# Sheet1.net
KiCad netlist of a schematic drawn in Altium Designer
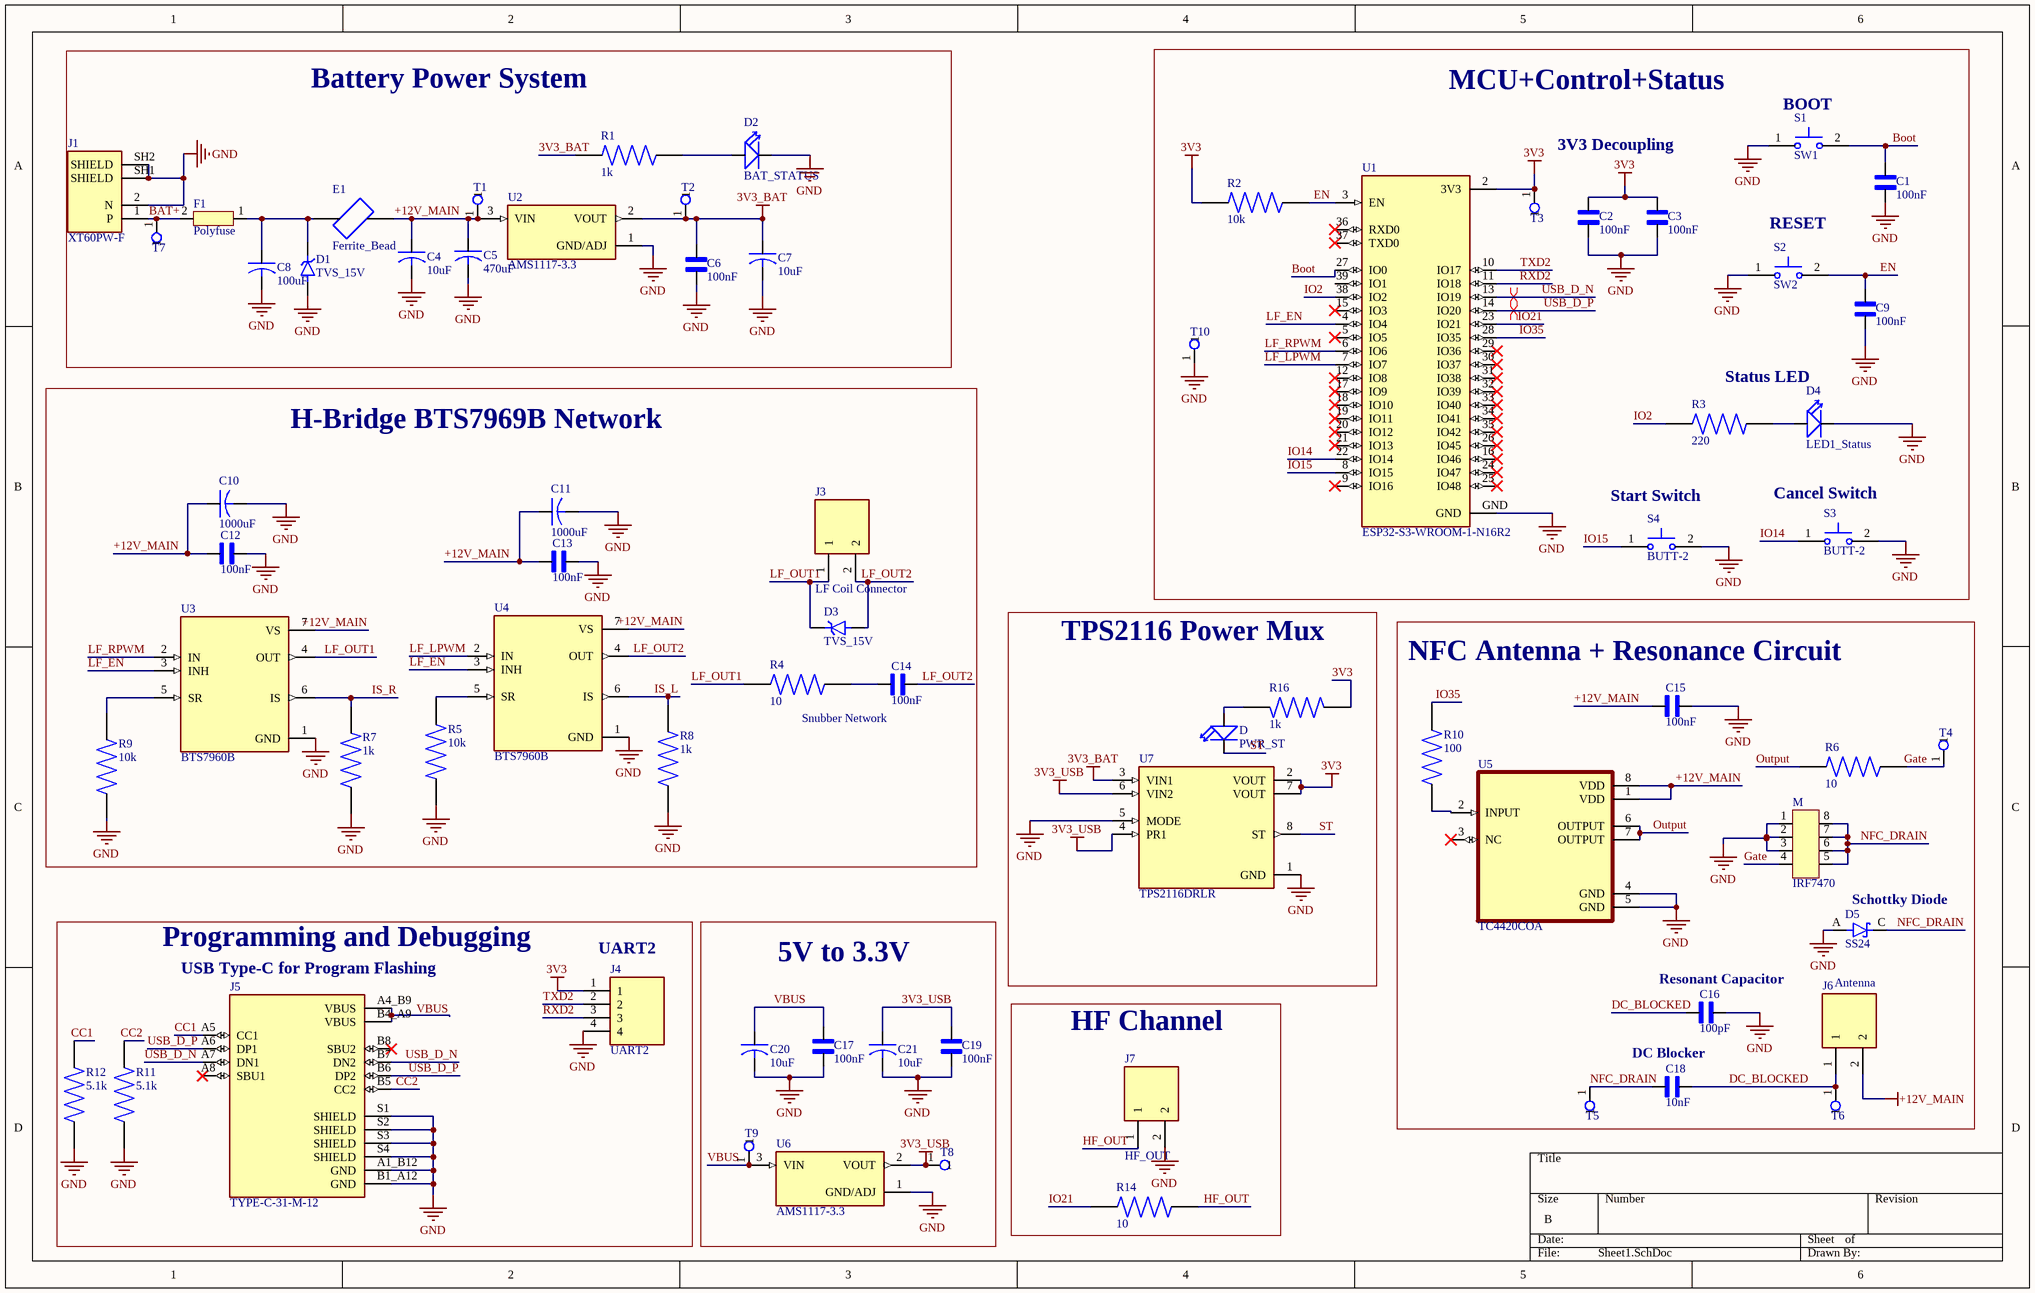
[diagram p0: Sheet1.SchDoc]

(export (version "E")
  (design (tool "Eeschema 10.0.6"))
  (components
    (comp (ref "C1")
      (value "100nF")
      (footprint "SMD_Ceramic_CAP")
      (description "10000 pF Â±5% 16V Ceramic Capacitor X7R 0805 (2012 Metric)")
      (fields (field (name "MF") "AVX") (field (name "MP") "0805YC103J4T2A"))
      (libsource (lib "Schlib1") (part "SMD_Ceramic_CAP"))
    )
    (comp (ref "C2")
      (value "100nF")
      (footprint "SMD_Ceramic_CAP")
      (description "10000 pF Â±5% 16V Ceramic Capacitor X7R 0805 (2012 Metric)")
      (fields (field (name "MF") "AVX") (field (name "MP") "0805YC103J4T2A"))
      (libsource (lib "Schlib1") (part "SMD_Ceramic_CAP"))
    )
    (comp (ref "C3")
      (value "100nF")
      (footprint "SMD_Ceramic_CAP")
      (description "10000 pF Â±5% 16V Ceramic Capacitor X7R 0805 (2012 Metric)")
      (fields (field (name "MF") "AVX") (field (name "MP") "0805YC103J4T2A"))
      (libsource (lib "Schlib1") (part "SMD_Ceramic_CAP"))
    )
    (comp (ref "C4")
      (value "10uF")
      (footprint "Capacitor_Bipolar-SMD")
      (description "<B>CAPACITOR</B>, American symbol")
      (fields (field (name "MP") "CAPACITOR"))
      (libsource (lib "Schlib1") (part "CAPACITOR"))
    )
    (comp (ref "C5")
      (value "470uF")
      (footprint "Capacitor_Bipolar-SMD")
      (description "<B>CAPACITOR</B>, American symbol")
      (fields (field (name "MP") "CAPACITOR"))
      (libsource (lib "Schlib1") (part "CAPACITOR"))
    )
    (comp (ref "C6")
      (value "100nF")
      (footprint "SMD_Ceramic_CAP")
      (description "10000 pF Â±5% 16V Ceramic Capacitor X7R 0805 (2012 Metric)")
      (fields (field (name "MF") "AVX") (field (name "MP") "0805YC103J4T2A"))
      (libsource (lib "Schlib1") (part "SMD_Ceramic_CAP"))
    )
    (comp (ref "C7")
      (value "10uF")
      (footprint "Capacitor_Bipolar-SMD")
      (description "<B>CAPACITOR</B>, American symbol")
      (fields (field (name "MP") "CAPACITOR"))
      (libsource (lib "Schlib1") (part "CAPACITOR"))
    )
    (comp (ref "C8")
      (value "100uF")
      (footprint "Capacitor_Bipolar-SMD")
      (description "<B>CAPACITOR</B>, American symbol")
      (fields (field (name "MP") "CAPACITOR"))
      (libsource (lib "Schlib1") (part "CAPACITOR"))
    )
    (comp (ref "C9")
      (value "100nF")
      (footprint "SMD_Ceramic_CAP")
      (description "10000 pF Â±5% 16V Ceramic Capacitor X7R 0805 (2012 Metric)")
      (fields (field (name "MF") "AVX") (field (name "MP") "0805YC103J4T2A"))
      (libsource (lib "Schlib1") (part "SMD_Ceramic_CAP"))
    )
    (comp (ref "C10")
      (value "1000uF")
      (footprint "Capacitor_Bipolar-SMD")
      (description "<B>CAPACITOR</B>, American symbol")
      (fields (field (name "MP") "CAPACITOR"))
      (libsource (lib "Schlib1") (part "CAPACITOR"))
    )
    (comp (ref "C11")
      (value "1000uF")
      (footprint "Capacitor_Bipolar-SMD")
      (description "<B>CAPACITOR</B>, American symbol")
      (fields (field (name "MP") "CAPACITOR"))
      (libsource (lib "Schlib1") (part "CAPACITOR"))
    )
    (comp (ref "C12")
      (value "100nF")
      (footprint "SMD_Ceramic_CAP")
      (description "10000 pF Â±5% 16V Ceramic Capacitor X7R 0805 (2012 Metric)")
      (fields (field (name "MF") "AVX") (field (name "MP") "0805YC103J4T2A"))
      (libsource (lib "") (part "SMD_Ceramic_CAP_1"))
    )
    (comp (ref "C13")
      (value "100nF")
      (footprint "SMD_Ceramic_CAP")
      (description "10000 pF Â±5% 16V Ceramic Capacitor X7R 0805 (2012 Metric)")
      (fields (field (name "MF") "AVX") (field (name "MP") "0805YC103J4T2A"))
      (libsource (lib "") (part "SMD_Ceramic_CAP_1"))
    )
    (comp (ref "C14")
      (value "100nF")
      (footprint "SMD_Ceramic_CAP")
      (description "10000 pF Â±5% 16V Ceramic Capacitor X7R 0805 (2012 Metric)")
      (fields (field (name "MF") "AVX") (field (name "MP") "0805YC103J4T2A"))
      (libsource (lib "") (part "SMD_Ceramic_CAP_1"))
    )
    (comp (ref "C15")
      (value "100nF")
      (footprint "SMD_Ceramic_CAP")
      (description "10000 pF Â±5% 16V Ceramic Capacitor X7R 0805 (2012 Metric)")
      (fields (field (name "MF") "AVX") (field (name "MP") "0805YC103J4T2A"))
      (libsource (lib "") (part "SMD_Ceramic_CAP_2"))
    )
    (comp (ref "C16")
      (value "100pF")
      (footprint "SMD_Ceramic_CAP")
      (description "10000 pF Â±5% 16V Ceramic Capacitor X7R 0805 (2012 Metric)")
      (fields (field (name "MF") "AVX") (field (name "MP") "0805YC103J4T2A"))
      (libsource (lib "") (part "SMD_Ceramic_CAP_1"))
    )
    (comp (ref "C17")
      (value "100nF")
      (footprint "SMD_Ceramic_CAP")
      (description "10000 pF Â±5% 16V Ceramic Capacitor X7R 0805 (2012 Metric)")
      (fields (field (name "MF") "AVX") (field (name "MP") "0805YC103J4T2A"))
      (libsource (lib "Schlib1") (part "SMD_Ceramic_CAP"))
    )
    (comp (ref "C18")
      (value "10nF")
      (footprint "SMD_Ceramic_CAP")
      (description "10000 pF Â±5% 16V Ceramic Capacitor X7R 0805 (2012 Metric)")
      (fields (field (name "MF") "AVX") (field (name "MP") "0805YC103J4T2A"))
      (libsource (lib "") (part "SMD_Ceramic_CAP_1"))
    )
    (comp (ref "C19")
      (value "100nF")
      (footprint "SMD_Ceramic_CAP")
      (description "10000 pF Â±5% 16V Ceramic Capacitor X7R 0805 (2012 Metric)")
      (fields (field (name "MF") "AVX") (field (name "MP") "0805YC103J4T2A"))
      (libsource (lib "Schlib1") (part "SMD_Ceramic_CAP"))
    )
    (comp (ref "C20")
      (value "10uF")
      (footprint "Capacitor_Bipolar-SMD")
      (description "<B>CAPACITOR</B>, American symbol")
      (fields (field (name "MP") "CAPACITOR"))
      (libsource (lib "Schlib1") (part "CAPACITOR"))
    )
    (comp (ref "C21")
      (value "10uF")
      (footprint "Capacitor_Bipolar-SMD")
      (description "<B>CAPACITOR</B>, American symbol")
      (fields (field (name "MP") "CAPACITOR"))
      (libsource (lib "Schlib1") (part "CAPACITOR"))
    )
    (comp (ref "D")
      (value "PWR_ST")
      (footprint "SnapEDApcb:LED-0603")
      (description "Blue LED Indication - Discrete 2.8V 0603 _1608 Metric_")
      (fields (field (name "MF") "Everlight") (field (name "MP") "19-217/BHC-ZL1M2RY/3T"))
      (libsource (lib "Schlib1") (part "SMD-LED(0603)"))
    )
    (comp (ref "D1")
      (value "TVS_15V")
      (footprint "TVS_15V")
      (description "15V Clamp 80A Ipp Tvs Diode Surface Mount SGP1610N2")
      (fields (field (name "MF") "Semtech Corporation") (field (name "MP") "UCLAMP0571P.TNT"))
      (libsource (lib "Schlib1") (part "TVS_15V"))
    )
    (comp (ref "D2")
      (value "BAT_STATUS")
      (footprint "SnapEDApcb:LED-0603")
      (description "Blue LED Indication - Discrete 2.8V 0603 _1608 Metric_")
      (fields (field (name "MF") "Everlight") (field (name "MP") "19-217/BHC-ZL1M2RY/3T"))
      (libsource (lib "Schlib1") (part "SMD-LED(0603)"))
    )
    (comp (ref "D3")
      (value "TVS_15V")
      (footprint "TVS_15V")
      (description "15V Clamp 80A Ipp Tvs Diode Surface Mount SGP1610N2")
      (fields (field (name "MF") "Semtech Corporation") (field (name "MP") "UCLAMP0571P.TNT"))
      (libsource (lib "Schlib1") (part "TVS_15V"))
    )
    (comp (ref "D4")
      (value "LED1_Status")
      (footprint "SnapEDApcb:LED-0603")
      (description "Blue LED Indication - Discrete 2.8V 0603 _1608 Metric_")
      (fields (field (name "MF") "Everlight") (field (name "MP") "19-217/BHC-ZL1M2RY/3T"))
      (libsource (lib "Schlib1") (part "SMD-LED(0603)"))
    )
    (comp (ref "D5")
      (value "SS24")
      (footprint "SS24")
      (description "Diode Schottky 40V 2A Surface Mount DO-214AA (SMB)")
      (fields (field (name "MF") "ON Semiconductor"))
      (libsource (lib "Schlib1") (part "SS24"))
    )
    (comp (ref "E1")
      (value "Ferrite_Bead")
      (footprint "Ferrite_bead")
      (description "120 Ohms @ 100 MHz 1 Power, Signal Line Ferrite Bead 0603 (1608 Metric) 700mA 200mOhm")
      (fields (field (name "MF") "Laird") (field (name "MP") "LI0603G121R-10"))
      (libsource (lib "Schlib1") (part "Ferrite_Bead"))
    )
    (comp (ref "F1") (value "Polyfuse") (footprint "Polyfuse") (libsource (lib "Schlib1") (part "Polyfuse")))
    (comp (ref "J1")
      (value "XT60PW-F")
      (footprint "XT60PW-F")
      (description "Connector: DC supply; socket; female; XT60; 30A; 500V; PIN: 2; THT")
      (fields (field (name "MF") "AMASS"))
      (libsource (lib "Schlib1") (part "XT60PW-F"))
    )
    (comp (ref "J3")
      (value "LF Coil Connector")
      (footprint "2_Pin_Terminal_Block")
      (description "2 Pin Terminal Block 5mm Pitch")
      (fields (field (name "MF") "Handson Technology") (field (name "MP") "KF301-2P"))
      (libsource (lib "Schlib1") (part "2_Pin_Terminal_Block"))
    )
    (comp (ref "J4")
      (value "UART2")
      (footprint "JST_XH_Balance")
      (description "MTA-100 HEADER - TIN, 04P MTA100 HDR ASSY SQ R/A POL ¦ TE Connectivity 640455-4")
      (fields (field (name "MF") "TE Connectivity") (field (name "MP") "640455-4"))
      (libsource (lib "Schlib1") (part "4_pin_header"))
    )
    (comp (ref "J5")
      (value "TYPE-C-31-M-12")
      (footprint "HRO_TYPE-C-31-M-12")
      (description "USB Connectors 24 Receptacle 1 8.94*7.3mm RoHS")
      (fields (field (name "MF") "HRO Electronics Co., Ltd."))
      (libsource (lib "Schlib1") (part "TYPE-C-31-M-12"))
    )
    (comp (ref "J6")
      (value "Antenna")
      (footprint "2_Pin_Terminal_Block")
      (description "2 Pin Terminal Block 5mm Pitch")
      (fields (field (name "MF") "Handson Technology") (field (name "MP") "KF301-2P"))
      (libsource (lib "Schlib1") (part "2_Pin_Terminal_Block"))
    )
    (comp (ref "J7")
      (value "HF_OUT")
      (footprint "2_Pin_Terminal_Block")
      (description "2 Pin Terminal Block 5mm Pitch")
      (fields (field (name "MF") "Handson Technology") (field (name "MP") "KF301-2P"))
      (libsource (lib "Schlib1") (part "2_Pin_Terminal_Block"))
    )
    (comp (ref "M") (value "IRF7470") (footprint "IRF7470") (libsource (lib "Schlib1") (part "IRF7470")))
    (comp (ref "R1")
      (value "1k")
      (footprint "Resistor_SMD")
      (description "1 kOhms Â±0.5% 0.063W, 1/16W Chip Resistor 0603 (1608 Metric) - Thin Film")
      (fields (field (name "MF") "Susumu") (field (name "MP") "RR0816P-102-D"))
      (libsource (lib "Schlib1") (part "Resisto_SMD"))
    )
    (comp (ref "R2")
      (value "10k")
      (footprint "Resistor_SMD")
      (description "1 kOhms Â±0.5% 0.063W, 1/16W Chip Resistor 0603 (1608 Metric) - Thin Film")
      (fields (field (name "MF") "Susumu") (field (name "MP") "RR0816P-102-D"))
      (libsource (lib "Schlib1") (part "Resistor_SMD"))
    )
    (comp (ref "R3")
      (value "220")
      (footprint "Resistor_SMD")
      (description "1 kOhms Â±0.5% 0.063W, 1/16W Chip Resistor 0603 (1608 Metric) - Thin Film")
      (fields (field (name "MF") "Susumu") (field (name "MP") "RR0816P-102-D"))
      (libsource (lib "Schlib1") (part "Resistor_SMD"))
    )
    (comp (ref "R4")
      (value "10")
      (footprint "Resistor_SMD")
      (description "1 kOhms Â±0.5% 0.063W, 1/16W Chip Resistor 0603 (1608 Metric) - Thin Film")
      (fields (field (name "MF") "Susumu") (field (name "MP") "RR0816P-102-D"))
      (libsource (lib "Schlib1") (part "Resistor_SMD"))
    )
    (comp (ref "R5")
      (value "10k")
      (footprint "Resistor_SMD")
      (description "1 kOhms Â±0.5% 0.063W, 1/16W Chip Resistor 0603 (1608 Metric) - Thin Film")
      (fields (field (name "MF") "Susumu") (field (name "MP") "RR0816P-102-D"))
      (libsource (lib "Schlib1") (part "Resistor_SMD"))
    )
    (comp (ref "R6")
      (value "10")
      (footprint "Resistor_SMD")
      (description "1 kOhms Â±0.5% 0.063W, 1/16W Chip Resistor 0603 (1608 Metric) - Thin Film")
      (fields (field (name "MF") "Susumu") (field (name "MP") "RR0816P-102-D"))
      (libsource (lib "Schlib1") (part "Resistor_SMD"))
    )
    (comp (ref "R7")
      (value "1k")
      (footprint "Resistor_SMD")
      (description "1 kOhms Â±0.5% 0.063W, 1/16W Chip Resistor 0603 (1608 Metric) - Thin Film")
      (fields (field (name "MF") "Susumu") (field (name "MP") "RR0816P-102-D"))
      (libsource (lib "Schlib1") (part "Resistor_SMD"))
    )
    (comp (ref "R8")
      (value "1k")
      (footprint "Resistor_SMD")
      (description "1 kOhms Â±0.5% 0.063W, 1/16W Chip Resistor 0603 (1608 Metric) - Thin Film")
      (fields (field (name "MF") "Susumu") (field (name "MP") "RR0816P-102-D"))
      (libsource (lib "Schlib1") (part "Resistor_SMD"))
    )
    (comp (ref "R9")
      (value "10k")
      (footprint "Resistor_SMD")
      (description "1 kOhms Â±0.5% 0.063W, 1/16W Chip Resistor 0603 (1608 Metric) - Thin Film")
      (fields (field (name "MF") "Susumu") (field (name "MP") "RR0816P-102-D"))
      (libsource (lib "Schlib1") (part "Resistor_SMD"))
    )
    (comp (ref "R10")
      (value "100")
      (footprint "Resistor_SMD")
      (description "1 kOhms Â±0.5% 0.063W, 1/16W Chip Resistor 0603 (1608 Metric) - Thin Film")
      (fields (field (name "MF") "Susumu") (field (name "MP") "RR0816P-102-D"))
      (libsource (lib "Schlib1") (part "Resistor_SMD"))
    )
    (comp (ref "R11")
      (value "5.1k")
      (footprint "Resistor_SMD")
      (description "1 kOhms Â±0.5% 0.063W, 1/16W Chip Resistor 0603 (1608 Metric) - Thin Film")
      (fields (field (name "MF") "Susumu") (field (name "MP") "RR0816P-102-D"))
      (libsource (lib "Schlib1") (part "Resistor_SMD"))
    )
    (comp (ref "R12")
      (value "5.1k")
      (footprint "Resistor_SMD")
      (description "1 kOhms Â±0.5% 0.063W, 1/16W Chip Resistor 0603 (1608 Metric) - Thin Film")
      (fields (field (name "MF") "Susumu") (field (name "MP") "RR0816P-102-D"))
      (libsource (lib "Schlib1") (part "Resistor_SMD"))
    )
    (comp (ref "R14")
      (value "10")
      (footprint "Resistor_SMD")
      (description "1 kOhms Â±0.5% 0.063W, 1/16W Chip Resistor 0603 (1608 Metric) - Thin Film")
      (fields (field (name "MF") "Susumu") (field (name "MP") "RR0816P-102-D"))
      (libsource (lib "Schlib1") (part "Resistor_SMD"))
    )
    (comp (ref "R16")
      (value "1k")
      (footprint "Resistor_SMD")
      (description "1 kOhms Â±0.5% 0.063W, 1/16W Chip Resistor 0603 (1608 Metric) - Thin Film")
      (fields (field (name "MF") "Susumu") (field (name "MP") "RR0816P-102-D"))
      (libsource (lib "Schlib1") (part "Resistor_SMD"))
    )
    (comp (ref "S1")
      (value "SW1")
      (footprint "SW_BUTT-2")
      (description "Tactile Switches MINI PUSH BUTTON SWITCH 2-PIN QTY. 4")
      (fields (field (name "MF") "Gravitech") (field (name "MP") "BUTT-2"))
      (libsource (lib "Schlib1") (part "BUTT-2"))
    )
    (comp (ref "S2")
      (value "SW2")
      (footprint "SW_BUTT-2")
      (description "Tactile Switches MINI PUSH BUTTON SWITCH 2-PIN QTY. 4")
      (fields (field (name "MF") "Gravitech") (field (name "MP") "BUTT-2"))
      (libsource (lib "Schlib1") (part "BUTT-2"))
    )
    (comp (ref "S3")
      (value "BUTT-2")
      (footprint "SW_BUTT-2")
      (description "Tactile Switches MINI PUSH BUTTON SWITCH 2-PIN QTY. 4")
      (fields (field (name "MF") "Gravitech"))
      (libsource (lib "Schlib1") (part "BUTT-2"))
    )
    (comp (ref "S4")
      (value "BUTT-2")
      (footprint "SW_BUTT-2")
      (description "Tactile Switches MINI PUSH BUTTON SWITCH 2-PIN QTY. 4")
      (fields (field (name "MF") "Gravitech"))
      (libsource (lib "Schlib1") (part "BUTT-2"))
    )
    (comp (ref "T1")
      (value "Test_Point")
      (footprint "Test_Point")
      (libsource (lib "Schlib1") (part "Test_Point"))
    )
    (comp (ref "T2")
      (value "Test_Point")
      (footprint "Test_Point")
      (libsource (lib "Schlib1") (part "Test_Point"))
    )
    (comp (ref "T3")
      (value "Test_Point")
      (footprint "Test_Point")
      (libsource (lib "Schlib1") (part "Test_Point"))
    )
    (comp (ref "T4")
      (value "Test_Point")
      (footprint "Test_Point")
      (libsource (lib "Schlib1") (part "Test_Point"))
    )
    (comp (ref "T5")
      (value "Test_Point")
      (footprint "Test_Point")
      (libsource (lib "Schlib1") (part "Test_Point"))
    )
    (comp (ref "T6")
      (value "Test_Point")
      (footprint "Test_Point")
      (libsource (lib "Schlib1") (part "Test_Point"))
    )
    (comp (ref "T7")
      (value "Test_Point")
      (footprint "Test_Point")
      (libsource (lib "Schlib1") (part "Test_Point"))
    )
    (comp (ref "T8")
      (value "Test_Point")
      (footprint "Test_Point")
      (libsource (lib "Schlib1") (part "Test_Point"))
    )
    (comp (ref "T9")
      (value "Test_Point")
      (footprint "Test_Point")
      (libsource (lib "Schlib1") (part "Test_Point"))
    )
    (comp (ref "T10")
      (value "Test_Point")
      (footprint "Test_Point")
      (libsource (lib "Schlib1") (part "Test_Point"))
    )
    (comp (ref "U1")
      (value "ESP32-S3-WROOM-1-N16R2")
      (footprint "ESP32-S3-WROOM-1-N16R2")
      (description "Bluetooth, WiFi 802.11b/g/n, Bluetooth v5.0 Transceiver Module 2.4GHz PCB Trace Surface Mount")
      (fields (field (name "MF") "Espressif Systems") (field (name "MP") "ESP32S3WROOM1N16R2"))
      (libsource (lib "Schlib1") (part "ESP32-S3-WROOM-1-N16R2"))
    )
    (comp (ref "U2")
      (value "AMS1117-3.3")
      (footprint "AMS1117-5.0")
      (description "1A LOW DROPOUT VOLTAGE REGULATOR")
      (fields (field (name "MP") "AMS1117-5.0") (field (name "MF") "ams"))
      (libsource (lib "Schlib1") (part "AMS1117-5.0"))
    )
    (comp (ref "U3")
      (value "BTS7960B")
      (footprint "BTS7960B")
      (description "Half Bridge Driver DC Motors, General Purpose DMOS PG-TO263-7-1")
      (fields (field (name "MF") "Infineon"))
      (libsource (lib "Schlib1") (part "BTS7960B"))
    )
    (comp (ref "U4")
      (value "BTS7960B")
      (footprint "BTS7960B")
      (description "Half Bridge Driver DC Motors, General Purpose DMOS PG-TO263-7-1")
      (fields (field (name "MF") "Infineon"))
      (libsource (lib "Schlib1") (part "BTS7960B"))
    )
    (comp (ref "U5")
      (value "TC4420COA")
      (footprint "TC4420COA")
      (fields (field (name "MF") "Microchip Technology"))
      (libsource (lib "Schlib1") (part "TC4420COA"))
    )
    (comp (ref "U6")
      (value "AMS1117-3.3")
      (footprint "AMS1117-5.0")
      (description "1A LOW DROPOUT VOLTAGE REGULATOR")
      (fields (field (name "MP") "AMS1117-5.0") (field (name "MF") "ams"))
      (libsource (lib "Schlib1") (part "AMS1117-5.0"))
    )
    (comp (ref "U7")
      (value "TPS2116DRLR")
      (footprint "TPS2116")
      (description "1.6-V to 5.5-V, 40-mâ„¦, 2.5-A, low-IQ, priority power multiplexer")
      (fields (field (name "MF") "Texas Instruments"))
      (libsource (lib "Schlib1") (part "TPS2116DRLR"))
    )
  )
  (nets
    (net (code "1") (name "+12V_MAIN") (class "Default")
      (node (ref "C10") (pin "1") (pinfunction "1_1") (pintype "passive"))
      (node (ref "C11") (pin "1") (pinfunction "1_1") (pintype "passive"))
      (node (ref "C12") (pin "1") (pinfunction "1_1") (pintype "passive"))
      (node (ref "C13") (pin "1") (pinfunction "1_1") (pintype "passive"))
      (node (ref "C15") (pin "2") (pinfunction "2_2") (pintype "passive"))
      (node (ref "C4") (pin "1") (pinfunction "1_1") (pintype "passive"))
      (node (ref "C5") (pin "1") (pinfunction "1_1") (pintype "passive"))
      (node (ref "E1") (pin "2") (pinfunction "2_2") (pintype "passive"))
      (node (ref "J6") (pin "2") (pinfunction "2_2") (pintype "passive"))
      (node (ref "T1") (pin "1") (pinfunction "1_1") (pintype "passive"))
      (node (ref "U2") (pin "3") (pinfunction "VIN_3") (pintype "input"))
      (node (ref "U3") (pin "7") (pinfunction "VS_7") (pintype "power_in"))
      (node (ref "U4") (pin "7") (pinfunction "VS_7") (pintype "power_in"))
      (node (ref "U5") (pin "1") (pinfunction "VDD_1") (pintype "power_in"))
      (node (ref "U5") (pin "8") (pinfunction "VDD_8") (pintype "power_in"))
    )
    (net (code "3") (name "/BAT+") (class "Default")
      (node (ref "F1") (pin "2") (pinfunction "2_2") (pintype "passive"))
      (node (ref "J1") (pin "1") (pinfunction "P_1") (pintype "passive"))
      (node (ref "T7") (pin "1") (pinfunction "1_1") (pintype "passive"))
    )
    (net (code "4") (name "/Boot") (class "Default")
      (node (ref "C1") (pin "2") (pinfunction "2_2") (pintype "passive"))
      (node (ref "S1") (pin "2") (pinfunction "2_2") (pintype "passive"))
      (node (ref "U1") (pin "27") (pinfunction "IO0_27") (pintype "bidirectional"))
    )
    (net (code "5") (name "/CC1") (class "Default")
      (node (ref "J5") (pin "A5") (pinfunction "CC1_A5") (pintype "bidirectional"))
      (node (ref "R12") (pin "2") (pinfunction "2_2") (pintype "passive"))
    )
    (net (code "6") (name "/CC2") (class "Default")
      (node (ref "J5") (pin "B5") (pinfunction "CC2_B5") (pintype "bidirectional"))
      (node (ref "R11") (pin "2") (pinfunction "2_2") (pintype "passive"))
    )
    (net (code "7") (name "/DC_BLOCKED") (class "Default")
      (node (ref "C16") (pin "1") (pinfunction "1_1") (pintype "passive"))
      (node (ref "C18") (pin "2") (pinfunction "2_2") (pintype "passive"))
      (node (ref "J6") (pin "1") (pinfunction "1_1") (pintype "passive"))
      (node (ref "T6") (pin "1") (pinfunction "1_1") (pintype "passive"))
    )
    (net (code "8") (name "/EN") (class "Default")
      (node (ref "C9") (pin "2") (pinfunction "2_2") (pintype "passive"))
      (node (ref "R2") (pin "2") (pinfunction "2_2") (pintype "passive"))
      (node (ref "S2") (pin "2") (pinfunction "2_2") (pintype "passive"))
      (node (ref "U1") (pin "3") (pinfunction "EN_3") (pintype "input"))
    )
    (net (code "9") (name "/Gate") (class "Default")
      (node (ref "M") (pin "4") (pintype "power_in"))
      (node (ref "R6") (pin "2") (pinfunction "2_2") (pintype "passive"))
      (node (ref "T4") (pin "1") (pinfunction "1_1") (pintype "passive"))
    )
    (net (code "10") (name "/HF_OUT") (class "Default")
      (node (ref "J7") (pin "1") (pinfunction "1_1") (pintype "passive"))
      (node (ref "R14") (pin "2") (pinfunction "2_2") (pintype "passive"))
    )
    (net (code "11") (name "/IO2") (class "Default")
      (node (ref "R3") (pin "1") (pinfunction "1_1") (pintype "passive"))
      (node (ref "U1") (pin "38") (pinfunction "IO2_38") (pintype "bidirectional"))
    )
    (net (code "12") (name "/IO14") (class "Default")
      (node (ref "S3") (pin "1") (pinfunction "1_1") (pintype "passive"))
      (node (ref "U1") (pin "22") (pinfunction "IO14_22") (pintype "bidirectional"))
    )
    (net (code "13") (name "/IO15") (class "Default")
      (node (ref "S4") (pin "1") (pinfunction "1_1") (pintype "passive"))
      (node (ref "U1") (pin "8") (pinfunction "IO15_8") (pintype "bidirectional"))
    )
    (net (code "14") (name "/IO21") (class "Default")
      (node (ref "R14") (pin "1") (pinfunction "1_1") (pintype "passive"))
      (node (ref "U1") (pin "23") (pinfunction "IO21_23") (pintype "bidirectional"))
    )
    (net (code "15") (name "/IO35") (class "Default")
      (node (ref "R10") (pin "1") (pinfunction "1_1") (pintype "passive"))
      (node (ref "U1") (pin "28") (pinfunction "IO35_28") (pintype "bidirectional"))
    )
    (net (code "16") (name "/IS_L") (class "Default")
      (node (ref "R8") (pin "2") (pinfunction "2_2") (pintype "passive"))
      (node (ref "U4") (pin "6") (pinfunction "IS_6") (pintype "output"))
    )
    (net (code "17") (name "/IS_R") (class "Default")
      (node (ref "R7") (pin "2") (pinfunction "2_2") (pintype "passive"))
      (node (ref "U3") (pin "6") (pinfunction "IS_6") (pintype "output"))
    )
    (net (code "18") (name "/LF_EN") (class "Default")
      (node (ref "U1") (pin "4") (pinfunction "IO4_4") (pintype "bidirectional"))
      (node (ref "U3") (pin "3") (pinfunction "INH_3") (pintype "input"))
      (node (ref "U4") (pin "3") (pinfunction "INH_3") (pintype "input"))
    )
    (net (code "19") (name "/LF_LPWM") (class "Default")
      (node (ref "U1") (pin "7") (pinfunction "IO7_7") (pintype "bidirectional"))
      (node (ref "U4") (pin "2") (pinfunction "IN_2") (pintype "input"))
    )
    (net (code "20") (name "/LF_OUT1") (class "Default")
      (node (ref "D3") (pin "K") (pinfunction "K_K") (pintype "passive"))
      (node (ref "J3") (pin "1") (pinfunction "1_1") (pintype "passive"))
      (node (ref "R4") (pin "1") (pinfunction "1_1") (pintype "passive"))
      (node (ref "U3") (pin "4") (pinfunction "OUT_4") (pintype "output"))
    )
    (net (code "21") (name "/LF_OUT2") (class "Default")
      (node (ref "C14") (pin "2") (pinfunction "2_2") (pintype "passive"))
      (node (ref "D3") (pin "A") (pinfunction "A_A") (pintype "passive"))
      (node (ref "J3") (pin "2") (pinfunction "2_2") (pintype "passive"))
      (node (ref "U4") (pin "4") (pinfunction "OUT_4") (pintype "output"))
    )
    (net (code "22") (name "/LF_RPWM") (class "Default")
      (node (ref "U1") (pin "6") (pinfunction "IO6_6") (pintype "bidirectional"))
      (node (ref "U3") (pin "2") (pinfunction "IN_2") (pintype "input"))
    )
    (net (code "23") (name "/NFC_DRAIN") (class "Default")
      (node (ref "C18") (pin "1") (pinfunction "1_1") (pintype "passive"))
      (node (ref "D5") (pin "C") (pinfunction "K_C") (pintype "passive"))
      (node (ref "M") (pin "5") (pintype "power_in"))
      (node (ref "M") (pin "6") (pintype "power_in"))
      (node (ref "M") (pin "7") (pintype "power_in"))
      (node (ref "M") (pin "8") (pintype "power_in"))
      (node (ref "T5") (pin "1") (pinfunction "1_1") (pintype "passive"))
    )
    (net (code "24") (name "/Output") (class "Default")
      (node (ref "R6") (pin "1") (pinfunction "1_1") (pintype "passive"))
      (node (ref "U5") (pin "6") (pinfunction "OUTPUT_6") (pintype "power_in"))
      (node (ref "U5") (pin "7") (pinfunction "OUTPUT_7") (pintype "power_in"))
    )
    (net (code "25") (name "/RXD2") (class "Default")
      (node (ref "J4") (pin "3") (pinfunction "3_3") (pintype "passive"))
      (node (ref "U1") (pin "11") (pinfunction "IO18_11") (pintype "bidirectional"))
    )
    (net (code "26") (name "/ST") (class "Default")
      (node (ref "D") (pin "NEG") (pinfunction "NEG_NEG") (pintype "passive"))
      (node (ref "U7") (pin "8") (pinfunction "ST_8") (pintype "output"))
    )
    (net (code "27") (name "/TXD2") (class "Default")
      (node (ref "J4") (pin "2") (pinfunction "2_2") (pintype "passive"))
      (node (ref "U1") (pin "10") (pinfunction "IO17_10") (pintype "bidirectional"))
    )
    (net (code "28") (name "/USB_D_N") (class "Default")
      (node (ref "J5") (pin "A7") (pinfunction "DN1_A7") (pintype "bidirectional"))
      (node (ref "J5") (pin "B7") (pinfunction "DN2_B7") (pintype "bidirectional"))
      (node (ref "U1") (pin "13") (pinfunction "IO19_13") (pintype "bidirectional"))
    )
    (net (code "29") (name "/USB_D_P") (class "Default")
      (node (ref "J5") (pin "A6") (pinfunction "DP1_A6") (pintype "bidirectional"))
      (node (ref "J5") (pin "B6") (pinfunction "DP2_B6") (pintype "bidirectional"))
      (node (ref "U1") (pin "14") (pinfunction "IO20_14") (pintype "bidirectional"))
    )
    (net (code "30") (name "/VBUS") (class "Default")
      (node (ref "C17") (pin "2") (pinfunction "2_2") (pintype "passive"))
      (node (ref "C20") (pin "1") (pinfunction "1_1") (pintype "passive"))
      (node (ref "J5") (pin "A4_B9") (pinfunction "VBUS_A4_B9") (pintype "power_in"))
      (node (ref "J5") (pin "B4_A9") (pinfunction "VBUS_B4_A9") (pintype "power_in"))
      (node (ref "T9") (pin "1") (pinfunction "1_1") (pintype "passive"))
      (node (ref "U6") (pin "3") (pinfunction "VIN_3") (pintype "input"))
    )
    (net (code "31") (name "3V3") (class "Default")
      (node (ref "C2") (pin "2") (pinfunction "2_2") (pintype "passive"))
      (node (ref "C3") (pin "2") (pinfunction "2_2") (pintype "passive"))
      (node (ref "J4") (pin "1") (pinfunction "1_1") (pintype "passive"))
      (node (ref "R16") (pin "1") (pinfunction "1_1") (pintype "passive"))
      (node (ref "R2") (pin "1") (pinfunction "1_1") (pintype "passive"))
      (node (ref "T3") (pin "1") (pinfunction "1_1") (pintype "passive"))
      (node (ref "U1") (pin "2") (pinfunction "3V3_2") (pintype "power_in"))
      (node (ref "U7") (pin "2") (pinfunction "VOUT_2") (pintype "power_in"))
      (node (ref "U7") (pin "7") (pinfunction "VOUT_7") (pintype "power_in"))
    )
    (net (code "32") (name "3V3_BAT") (class "Default")
      (node (ref "C6") (pin "2") (pinfunction "2_2") (pintype "passive"))
      (node (ref "C7") (pin "1") (pinfunction "1_1") (pintype "passive"))
      (node (ref "R1") (pin "1") (pinfunction "1_1") (pintype "passive"))
      (node (ref "T2") (pin "1") (pinfunction "1_1") (pintype "passive"))
      (node (ref "U2") (pin "2") (pinfunction "VOUT_2") (pintype "output"))
      (node (ref "U7") (pin "3") (pinfunction "VIN1_3") (pintype "input"))
    )
    (net (code "33") (name "3V3_USB") (class "Default")
      (node (ref "C19") (pin "2") (pinfunction "2_2") (pintype "passive"))
      (node (ref "C21") (pin "1") (pinfunction "1_1") (pintype "passive"))
      (node (ref "T8") (pin "1") (pinfunction "1_1") (pintype "passive"))
      (node (ref "U6") (pin "2") (pinfunction "VOUT_2") (pintype "output"))
      (node (ref "U7") (pin "4") (pinfunction "PR1_4") (pintype "input"))
      (node (ref "U7") (pin "6") (pinfunction "VIN2_6") (pintype "input"))
    )
    (net (code "34") (name "GND") (class "Default")
      (node (ref "C1") (pin "1") (pinfunction "1_1") (pintype "passive"))
      (node (ref "C10") (pin "2") (pinfunction "2_2") (pintype "passive"))
      (node (ref "C11") (pin "2") (pinfunction "2_2") (pintype "passive"))
      (node (ref "C12") (pin "2") (pinfunction "2_2") (pintype "passive"))
      (node (ref "C13") (pin "2") (pinfunction "2_2") (pintype "passive"))
      (node (ref "C15") (pin "1") (pinfunction "1_1") (pintype "passive"))
      (node (ref "C16") (pin "2") (pinfunction "2_2") (pintype "passive"))
      (node (ref "C17") (pin "1") (pinfunction "1_1") (pintype "passive"))
      (node (ref "C19") (pin "1") (pinfunction "1_1") (pintype "passive"))
      (node (ref "C2") (pin "1") (pinfunction "1_1") (pintype "passive"))
      (node (ref "C20") (pin "2") (pinfunction "2_2") (pintype "passive"))
      (node (ref "C21") (pin "2") (pinfunction "2_2") (pintype "passive"))
      (node (ref "C3") (pin "1") (pinfunction "1_1") (pintype "passive"))
      (node (ref "C4") (pin "2") (pinfunction "2_2") (pintype "passive"))
      (node (ref "C5") (pin "2") (pinfunction "2_2") (pintype "passive"))
      (node (ref "C6") (pin "1") (pinfunction "1_1") (pintype "passive"))
      (node (ref "C7") (pin "2") (pinfunction "2_2") (pintype "passive"))
      (node (ref "C8") (pin "2") (pinfunction "2_2") (pintype "passive"))
      (node (ref "C9") (pin "1") (pinfunction "1_1") (pintype "passive"))
      (node (ref "D1") (pin "A") (pinfunction "A_A") (pintype "passive"))
      (node (ref "D2") (pin "NEG") (pinfunction "NEG_NEG") (pintype "passive"))
      (node (ref "D4") (pin "NEG") (pinfunction "NEG_NEG") (pintype "passive"))
      (node (ref "D5") (pin "A") (pinfunction "A_A") (pintype "passive"))
      (node (ref "J1") (pin "2") (pinfunction "N_2") (pintype "passive"))
      (node (ref "J1") (pin "SH1") (pinfunction "SHIELD_SH1") (pintype "passive"))
      (node (ref "J1") (pin "SH2") (pinfunction "SHIELD_SH2") (pintype "passive"))
      (node (ref "J4") (pin "4") (pinfunction "4_4") (pintype "passive"))
      (node (ref "J5") (pin "A1_B12") (pinfunction "GND_A1_B12") (pintype "power_in"))
      (node (ref "J5") (pin "B1_A12") (pinfunction "GND_B1_A12") (pintype "power_in"))
      (node (ref "J5") (pin "S1") (pinfunction "SHIELD_S1") (pintype "passive"))
      (node (ref "J5") (pin "S2") (pinfunction "SHIELD_S2") (pintype "passive"))
      (node (ref "J5") (pin "S3") (pinfunction "SHIELD_S3") (pintype "passive"))
      (node (ref "J5") (pin "S4") (pinfunction "SHIELD_S4") (pintype "passive"))
      (node (ref "J7") (pin "2") (pinfunction "2_2") (pintype "passive"))
      (node (ref "M") (pin "1") (pintype "power_in"))
      (node (ref "M") (pin "2") (pintype "power_in"))
      (node (ref "M") (pin "3") (pintype "power_in"))
      (node (ref "R11") (pin "1") (pinfunction "1_1") (pintype "passive"))
      (node (ref "R12") (pin "1") (pinfunction "1_1") (pintype "passive"))
      (node (ref "R5") (pin "1") (pinfunction "1_1") (pintype "passive"))
      (node (ref "R7") (pin "1") (pinfunction "1_1") (pintype "passive"))
      (node (ref "R8") (pin "1") (pinfunction "1_1") (pintype "passive"))
      (node (ref "R9") (pin "1") (pinfunction "1_1") (pintype "passive"))
      (node (ref "S1") (pin "1") (pinfunction "1_1") (pintype "passive"))
      (node (ref "S2") (pin "1") (pinfunction "1_1") (pintype "passive"))
      (node (ref "S3") (pin "2") (pinfunction "2_2") (pintype "passive"))
      (node (ref "S4") (pin "2") (pinfunction "2_2") (pintype "passive"))
      (node (ref "T10") (pin "1") (pinfunction "1_1") (pintype "passive"))
      (node (ref "U1") (pin "GND") (pinfunction "GND_GND") (pintype "power_in"))
      (node (ref "U2") (pin "1") (pinfunction "GND/ADJ_1") (pintype "power_in"))
      (node (ref "U3") (pin "1") (pinfunction "GND_1") (pintype "power_in"))
      (node (ref "U4") (pin "1") (pinfunction "GND_1") (pintype "power_in"))
      (node (ref "U5") (pin "4") (pinfunction "GND_4") (pintype "power_in"))
      (node (ref "U5") (pin "5") (pinfunction "GND_5") (pintype "power_in"))
      (node (ref "U6") (pin "1") (pinfunction "GND/ADJ_1") (pintype "power_in"))
      (node (ref "U7") (pin "1") (pinfunction "GND_1") (pintype "power_in"))
      (node (ref "U7") (pin "5") (pinfunction "MODE_5") (pintype "input"))
    )
    (net (code "35") (name "Net-(C8-Pad1)") (class "Default")
      (node (ref "C8") (pin "1") (pinfunction "1_1") (pintype "passive"))
      (node (ref "D1") (pin "K") (pinfunction "K_K") (pintype "passive"))
      (node (ref "E1") (pin "1") (pinfunction "1_1") (pintype "passive"))
      (node (ref "F1") (pin "1") (pinfunction "1_1") (pintype "passive"))
    )
    (net (code "36") (name "Net-(C14-Pad1)") (class "Default")
      (node (ref "C14") (pin "1") (pinfunction "1_1") (pintype "passive"))
      (node (ref "R4") (pin "2") (pinfunction "2_2") (pintype "passive"))
    )
    (net (code "37") (name "Net-(D-PadPOS)") (class "Default")
      (node (ref "D") (pin "POS") (pinfunction "POS_POS") (pintype "passive"))
      (node (ref "R16") (pin "2") (pinfunction "2_2") (pintype "passive"))
    )
    (net (code "38") (name "Net-(D2-PadPOS)") (class "Default")
      (node (ref "D2") (pin "POS") (pinfunction "POS_POS") (pintype "passive"))
      (node (ref "R1") (pin "2") (pinfunction "2_2") (pintype "passive"))
    )
    (net (code "39") (name "Net-(D4-PadPOS)") (class "Default")
      (node (ref "D4") (pin "POS") (pinfunction "POS_POS") (pintype "passive"))
      (node (ref "R3") (pin "2") (pinfunction "2_2") (pintype "passive"))
    )
    (net (code "40") (name "Net-(U3-SR)") (class "Default")
      (node (ref "R9") (pin "2") (pinfunction "2_2") (pintype "passive"))
      (node (ref "U3") (pin "5") (pinfunction "SR_5") (pintype "input"))
    )
    (net (code "41") (name "Net-(U4-SR)") (class "Default")
      (node (ref "R5") (pin "2") (pinfunction "2_2") (pintype "passive"))
      (node (ref "U4") (pin "5") (pinfunction "SR_5") (pintype "input"))
    )
    (net (code "42") (name "Net-(U5-INPUT)") (class "Default")
      (node (ref "R10") (pin "2") (pinfunction "2_2") (pintype "passive"))
      (node (ref "U5") (pin "2") (pinfunction "INPUT_2") (pintype "input"))
    )
    (net (code "43") (name "unconnected-(J5-SBU1-PadA8)") (class "Default")
      (node (ref "J5") (pin "A8") (pinfunction "SBU1_A8") (pintype "bidirectional+no_connect"))
    )
    (net (code "44") (name "unconnected-(J5-SBU2-PadB8)") (class "Default")
      (node (ref "J5") (pin "B8") (pinfunction "SBU2_B8") (pintype "bidirectional+no_connect"))
    )
    (net (code "45") (name "unconnected-(U1-IO1-Pad39)") (class "Default")
      (node (ref "U1") (pin "39") (pinfunction "IO1_39") (pintype "bidirectional"))
    )
    (net (code "46") (name "unconnected-(U1-IO3-Pad15)") (class "Default")
      (node (ref "U1") (pin "15") (pinfunction "IO3_15") (pintype "bidirectional+no_connect"))
    )
    (net (code "47") (name "unconnected-(U1-IO5-Pad5)") (class "Default")
      (node (ref "U1") (pin "5") (pinfunction "IO5_5") (pintype "bidirectional+no_connect"))
    )
    (net (code "48") (name "unconnected-(U1-IO8-Pad12)") (class "Default")
      (node (ref "U1") (pin "12") (pinfunction "IO8_12") (pintype "bidirectional+no_connect"))
    )
    (net (code "49") (name "unconnected-(U1-IO9-Pad17)") (class "Default")
      (node (ref "U1") (pin "17") (pinfunction "IO9_17") (pintype "bidirectional+no_connect"))
    )
    (net (code "50") (name "unconnected-(U1-IO10-Pad18)") (class "Default")
      (node (ref "U1") (pin "18") (pinfunction "IO10_18") (pintype "bidirectional+no_connect"))
    )
    (net (code "51") (name "unconnected-(U1-IO11-Pad19)") (class "Default")
      (node (ref "U1") (pin "19") (pinfunction "IO11_19") (pintype "bidirectional+no_connect"))
    )
    (net (code "52") (name "unconnected-(U1-IO12-Pad20)") (class "Default")
      (node (ref "U1") (pin "20") (pinfunction "IO12_20") (pintype "bidirectional+no_connect"))
    )
    (net (code "53") (name "unconnected-(U1-IO13-Pad21)") (class "Default")
      (node (ref "U1") (pin "21") (pinfunction "IO13_21") (pintype "bidirectional+no_connect"))
    )
    (net (code "54") (name "unconnected-(U1-IO16-Pad9)") (class "Default")
      (node (ref "U1") (pin "9") (pinfunction "IO16_9") (pintype "bidirectional+no_connect"))
    )
    (net (code "55") (name "unconnected-(U1-IO36-Pad29)") (class "Default")
      (node (ref "U1") (pin "29") (pinfunction "IO36_29") (pintype "bidirectional+no_connect"))
    )
    (net (code "56") (name "unconnected-(U1-IO37-Pad30)") (class "Default")
      (node (ref "U1") (pin "30") (pinfunction "IO37_30") (pintype "bidirectional+no_connect"))
    )
    (net (code "57") (name "unconnected-(U1-IO38-Pad31)") (class "Default")
      (node (ref "U1") (pin "31") (pinfunction "IO38_31") (pintype "bidirectional+no_connect"))
    )
    (net (code "58") (name "unconnected-(U1-IO39-Pad32)") (class "Default")
      (node (ref "U1") (pin "32") (pinfunction "IO39_32") (pintype "bidirectional+no_connect"))
    )
    (net (code "59") (name "unconnected-(U1-IO40-Pad33)") (class "Default")
      (node (ref "U1") (pin "33") (pinfunction "IO40_33") (pintype "bidirectional+no_connect"))
    )
    (net (code "60") (name "unconnected-(U1-IO41-Pad34)") (class "Default")
      (node (ref "U1") (pin "34") (pinfunction "IO41_34") (pintype "bidirectional+no_connect"))
    )
    (net (code "61") (name "unconnected-(U1-IO42-Pad35)") (class "Default")
      (node (ref "U1") (pin "35") (pinfunction "IO42_35") (pintype "bidirectional+no_connect"))
    )
    (net (code "62") (name "unconnected-(U1-IO45-Pad26)") (class "Default")
      (node (ref "U1") (pin "26") (pinfunction "IO45_26") (pintype "bidirectional+no_connect"))
    )
    (net (code "63") (name "unconnected-(U1-IO46-Pad16)") (class "Default")
      (node (ref "U1") (pin "16") (pinfunction "IO46_16") (pintype "bidirectional+no_connect"))
    )
    (net (code "64") (name "unconnected-(U1-IO47-Pad24)") (class "Default")
      (node (ref "U1") (pin "24") (pinfunction "IO47_24") (pintype "bidirectional+no_connect"))
    )
    (net (code "65") (name "unconnected-(U1-IO48-Pad25)") (class "Default")
      (node (ref "U1") (pin "25") (pinfunction "IO48_25") (pintype "bidirectional+no_connect"))
    )
    (net (code "66") (name "unconnected-(U1-RXD0-Pad36)") (class "Default")
      (node (ref "U1") (pin "36") (pinfunction "RXD0_36") (pintype "bidirectional+no_connect"))
    )
    (net (code "67") (name "unconnected-(U1-TXD0-Pad37)") (class "Default")
      (node (ref "U1") (pin "37") (pinfunction "TXD0_37") (pintype "bidirectional+no_connect"))
    )
    (net (code "68") (name "unconnected-(U5-NC-Pad3)") (class "Default")
      (node (ref "U5") (pin "3") (pinfunction "NC_3") (pintype "bidirectional+no_connect"))
    )
  )
)
